# Eeprom.net
KiCad netlist of a schematic drawn in Altium Designer
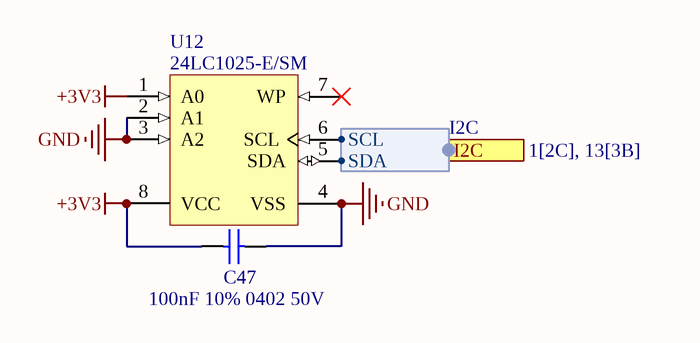
[diagram p0: Eeprom.SchDoc]

(export (version "E")
  (design (tool "Eeschema 10.0.6"))
  (components
    (comp (ref "C47")
      (value "100nF 10% 0402 50V")
      (footprint "0402N")
      (fields (field (name "TOLERANCE") "10") (field (name "VOLTAGE") "50"))
      (libsource (lib "MiscPassives") (part "C0402"))
    )
    (comp (ref "U12")
      (value "24LC1025-E/SM")
      (footprint "SOIJ-SM8_N")
      (description "1 Mbit, 400kHz, 2.5V, I2C Serial EEPROM, 8-Pin SOIC 208mil, Extended Temperature")
      (libsource (lib "Altium Content Vault") (part "MEM-SEEPROM-34AA02-IL8"))
    )
  )
  (nets
    (net (code "2") (name "+3V3") (class "Default")
      (node (ref "C47") (pin "2") (pinfunction "2_2") (pintype "passive"))
      (node (ref "U12") (pin "1") (pinfunction "A0_1") (pintype "input"))
      (node (ref "U12") (pin "8") (pinfunction "VCC_8") (pintype "power_in"))
    )
    (net (code "3") (name "/SCL") (class "Default")
      (node (ref "U12") (pin "6") (pinfunction "SCL_6") (pintype "input"))
    )
    (net (code "4") (name "/SDA") (class "Default")
      (node (ref "U12") (pin "5") (pinfunction "SDA_5") (pintype "bidirectional"))
    )
    (net (code "6") (name "GND") (class "Default")
      (node (ref "C47") (pin "1") (pinfunction "1_1") (pintype "passive"))
      (node (ref "U12") (pin "2") (pinfunction "A1_2") (pintype "input"))
      (node (ref "U12") (pin "3") (pinfunction "A2_3") (pintype "input"))
      (node (ref "U12") (pin "4") (pinfunction "VSS_4") (pintype "power_in"))
    )
    (net (code "7") (name "unconnected-(U12-WP-Pad7)") (class "Default")
      (node (ref "U12") (pin "7") (pinfunction "WP_7") (pintype "input+no_connect"))
    )
  )
)
